# GSWB.net
KiCad netlist of a schematic drawn in EAGLE
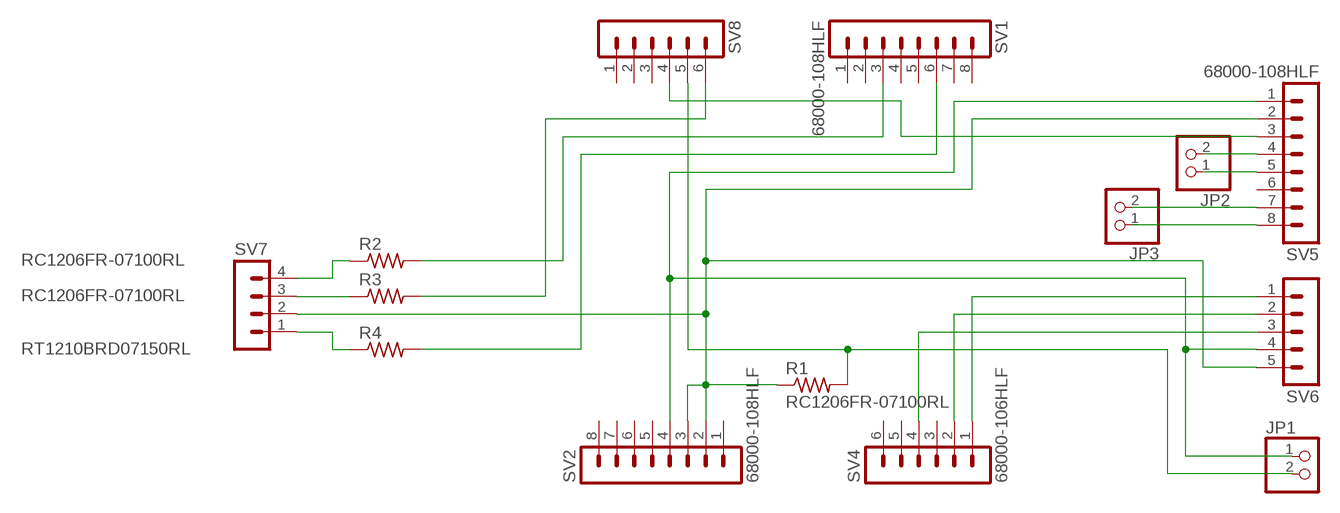
[diagram p0: schematic, sheet 1]

(export (version "E")
  (design (tool "Eeschema 10.0.6"))
  (components
    (comp (ref "JP1")
      (value "PINHD-1X2")
      (footprint "eagle-import:1X02")
      (libsource (lib "eagle-import") (part "PINHD-1X2"))
    )
    (comp (ref "JP2")
      (value "PINHD-1X2")
      (footprint "eagle-import:1X02")
      (libsource (lib "eagle-import") (part "PINHD-1X2"))
    )
    (comp (ref "JP3")
      (value "PINHD-1X2")
      (footprint "eagle-import:1X02")
      (libsource (lib "eagle-import") (part "PINHD-1X2"))
    )
    (comp (ref "R1")
      (value "RC1206FR-07100RL")
      (footprint "eagle-import:M1206")
      (libsource (lib "eagle-import") (part "R-US_M1206"))
    )
    (comp (ref "R2")
      (value "RC1206FR-07100RL")
      (footprint "eagle-import:M1206")
      (libsource (lib "eagle-import") (part "R-US_M1206"))
    )
    (comp (ref "R3")
      (value "RC1206FR-07100RL")
      (footprint "eagle-import:M1206")
      (libsource (lib "eagle-import") (part "R-US_M1206"))
    )
    (comp (ref "R4")
      (value "RT1210BRD07150RL")
      (footprint "eagle-import:M1206")
      (libsource (lib "eagle-import") (part "R-US_M1206"))
    )
    (comp (ref "SV1")
      (value "68000-108HLF")
      (footprint "eagle-import:MA08-1")
      (libsource (lib "eagle-import") (part "MA08-1"))
    )
    (comp (ref "SV2")
      (value "68000-108HLF")
      (footprint "eagle-import:MA08-1")
      (libsource (lib "eagle-import") (part "MA08-1"))
    )
    (comp (ref "SV4")
      (value "68000-106HLF")
      (footprint "eagle-import:MA06-1")
      (libsource (lib "eagle-import") (part "MA06-1"))
    )
    (comp (ref "SV5")
      (value "68000-108HLF")
      (footprint "eagle-import:MA08-1")
      (libsource (lib "eagle-import") (part "MA08-1"))
    )
    (comp (ref "SV6")
      (value "MA05-1")
      (footprint "eagle-import:MA05-1")
      (libsource (lib "eagle-import") (part "MA05-1"))
    )
    (comp (ref "SV7")
      (value "MA04-1")
      (footprint "eagle-import:MA04-1")
      (libsource (lib "eagle-import") (part "MA04-1"))
    )
    (comp (ref "SV8")
      (value "MA06-1")
      (footprint "eagle-import:MA06-1")
      (libsource (lib "eagle-import") (part "MA06-1"))
    )
  )
  (nets
    (net (code "1") (name "Net-(JP1-Pad1)") (class "Default")
      (node (ref "JP1") (pin "1") (pinfunction "1_1") (pintype "passive"))
      (node (ref "SV2") (pin "4") (pinfunction "4_4") (pintype "passive"))
      (node (ref "SV5") (pin "1") (pinfunction "1_1") (pintype "passive"))
      (node (ref "SV6") (pin "4") (pinfunction "4_4") (pintype "passive"))
    )
    (net (code "2") (name "Net-(JP1-Pad2)") (class "Default")
      (node (ref "JP1") (pin "2") (pinfunction "2_2") (pintype "passive"))
      (node (ref "R1") (pin "2") (pinfunction "2_2") (pintype "passive"))
      (node (ref "SV8") (pin "5") (pinfunction "5_5") (pintype "passive"))
    )
    (net (code "3") (name "Net-(JP2-Pad1)") (class "Default")
      (node (ref "JP2") (pin "1") (pinfunction "1_1") (pintype "passive"))
      (node (ref "SV5") (pin "5") (pinfunction "5_5") (pintype "passive"))
    )
    (net (code "4") (name "Net-(JP2-Pad2)") (class "Default")
      (node (ref "JP2") (pin "2") (pinfunction "2_2") (pintype "passive"))
      (node (ref "SV5") (pin "4") (pinfunction "4_4") (pintype "passive"))
    )
    (net (code "5") (name "Net-(JP3-Pad1)") (class "Default")
      (node (ref "JP3") (pin "1") (pinfunction "1_1") (pintype "passive"))
      (node (ref "SV5") (pin "8") (pinfunction "8_8") (pintype "passive"))
    )
    (net (code "6") (name "Net-(JP3-Pad2)") (class "Default")
      (node (ref "JP3") (pin "2") (pinfunction "2_2") (pintype "passive"))
      (node (ref "SV5") (pin "7") (pinfunction "7_7") (pintype "passive"))
    )
    (net (code "7") (name "Net-(R1-Pad1)") (class "Default")
      (node (ref "R1") (pin "1") (pinfunction "1_1") (pintype "passive"))
      (node (ref "SV2") (pin "2") (pinfunction "2_2") (pintype "passive"))
      (node (ref "SV2") (pin "3") (pinfunction "3_3") (pintype "passive"))
      (node (ref "SV5") (pin "2") (pinfunction "2_2") (pintype "passive"))
      (node (ref "SV6") (pin "5") (pinfunction "5_5") (pintype "passive"))
      (node (ref "SV7") (pin "2") (pinfunction "2_2") (pintype "passive"))
    )
    (net (code "8") (name "Net-(R2-Pad1)") (class "Default")
      (node (ref "R2") (pin "1") (pinfunction "1_1") (pintype "passive"))
      (node (ref "SV7") (pin "4") (pinfunction "4_4") (pintype "passive"))
    )
    (net (code "9") (name "Net-(R2-Pad2)") (class "Default")
      (node (ref "R2") (pin "2") (pinfunction "2_2") (pintype "passive"))
      (node (ref "SV1") (pin "3") (pinfunction "3_3") (pintype "passive"))
    )
    (net (code "10") (name "Net-(R3-Pad1)") (class "Default")
      (node (ref "R3") (pin "1") (pinfunction "1_1") (pintype "passive"))
      (node (ref "SV7") (pin "3") (pinfunction "3_3") (pintype "passive"))
    )
    (net (code "11") (name "Net-(R3-Pad2)") (class "Default")
      (node (ref "R3") (pin "2") (pinfunction "2_2") (pintype "passive"))
      (node (ref "SV8") (pin "6") (pinfunction "6_6") (pintype "passive"))
    )
    (net (code "12") (name "Net-(R4-Pad1)") (class "Default")
      (node (ref "R4") (pin "1") (pinfunction "1_1") (pintype "passive"))
      (node (ref "SV7") (pin "1") (pinfunction "1_1") (pintype "passive"))
    )
    (net (code "13") (name "Net-(R4-Pad2)") (class "Default")
      (node (ref "R4") (pin "2") (pinfunction "2_2") (pintype "passive"))
      (node (ref "SV1") (pin "6") (pinfunction "6_6") (pintype "passive"))
    )
    (net (code "14") (name "Net-(SV4-Pad1)") (class "Default")
      (node (ref "SV4") (pin "1") (pinfunction "1_1") (pintype "passive"))
      (node (ref "SV6") (pin "1") (pinfunction "1_1") (pintype "passive"))
    )
    (net (code "15") (name "Net-(SV4-Pad2)") (class "Default")
      (node (ref "SV4") (pin "2") (pinfunction "2_2") (pintype "passive"))
      (node (ref "SV6") (pin "2") (pinfunction "2_2") (pintype "passive"))
    )
    (net (code "16") (name "Net-(SV4-Pad4)") (class "Default")
      (node (ref "SV4") (pin "4") (pinfunction "4_4") (pintype "passive"))
      (node (ref "SV6") (pin "3") (pinfunction "3_3") (pintype "passive"))
    )
    (net (code "17") (name "Net-(SV5-Pad3)") (class "Default")
      (node (ref "SV5") (pin "3") (pinfunction "3_3") (pintype "passive"))
      (node (ref "SV8") (pin "4") (pinfunction "4_4") (pintype "passive"))
    )
    (net (code "18") (name "unconnected-(SV1-Pad1)") (class "Default")
      (node (ref "SV1") (pin "1") (pinfunction "1_1") (pintype "passive"))
    )
    (net (code "19") (name "unconnected-(SV1-Pad2)") (class "Default")
      (node (ref "SV1") (pin "2") (pinfunction "2_2") (pintype "passive"))
    )
    (net (code "20") (name "unconnected-(SV1-Pad4)") (class "Default")
      (node (ref "SV1") (pin "4") (pinfunction "4_4") (pintype "passive"))
    )
    (net (code "21") (name "unconnected-(SV1-Pad5)") (class "Default")
      (node (ref "SV1") (pin "5") (pinfunction "5_5") (pintype "passive"))
    )
    (net (code "22") (name "unconnected-(SV1-Pad7)") (class "Default")
      (node (ref "SV1") (pin "7") (pinfunction "7_7") (pintype "passive"))
    )
    (net (code "23") (name "unconnected-(SV1-Pad8)") (class "Default")
      (node (ref "SV1") (pin "8") (pinfunction "8_8") (pintype "passive"))
    )
    (net (code "24") (name "unconnected-(SV2-Pad1)") (class "Default")
      (node (ref "SV2") (pin "1") (pinfunction "1_1") (pintype "passive"))
    )
    (net (code "25") (name "unconnected-(SV2-Pad5)") (class "Default")
      (node (ref "SV2") (pin "5") (pinfunction "5_5") (pintype "passive"))
    )
    (net (code "26") (name "unconnected-(SV2-Pad6)") (class "Default")
      (node (ref "SV2") (pin "6") (pinfunction "6_6") (pintype "passive"))
    )
    (net (code "27") (name "unconnected-(SV2-Pad7)") (class "Default")
      (node (ref "SV2") (pin "7") (pinfunction "7_7") (pintype "passive"))
    )
    (net (code "28") (name "unconnected-(SV2-Pad8)") (class "Default")
      (node (ref "SV2") (pin "8") (pinfunction "8_8") (pintype "passive"))
    )
    (net (code "29") (name "unconnected-(SV4-Pad3)") (class "Default")
      (node (ref "SV4") (pin "3") (pinfunction "3_3") (pintype "passive"))
    )
    (net (code "30") (name "unconnected-(SV4-Pad5)") (class "Default")
      (node (ref "SV4") (pin "5") (pinfunction "5_5") (pintype "passive"))
    )
    (net (code "31") (name "unconnected-(SV4-Pad6)") (class "Default")
      (node (ref "SV4") (pin "6") (pinfunction "6_6") (pintype "passive"))
    )
    (net (code "32") (name "unconnected-(SV5-Pad6)") (class "Default")
      (node (ref "SV5") (pin "6") (pinfunction "6_6") (pintype "passive"))
    )
    (net (code "33") (name "unconnected-(SV8-Pad1)") (class "Default")
      (node (ref "SV8") (pin "1") (pinfunction "1_1") (pintype "passive"))
    )
    (net (code "34") (name "unconnected-(SV8-Pad2)") (class "Default")
      (node (ref "SV8") (pin "2") (pinfunction "2_2") (pintype "passive"))
    )
    (net (code "35") (name "unconnected-(SV8-Pad3)") (class "Default")
      (node (ref "SV8") (pin "3") (pinfunction "3_3") (pintype "passive"))
    )
  )
)
